# shield_scaffold.net
KiCad netlist of a schematic drawn in EAGLE
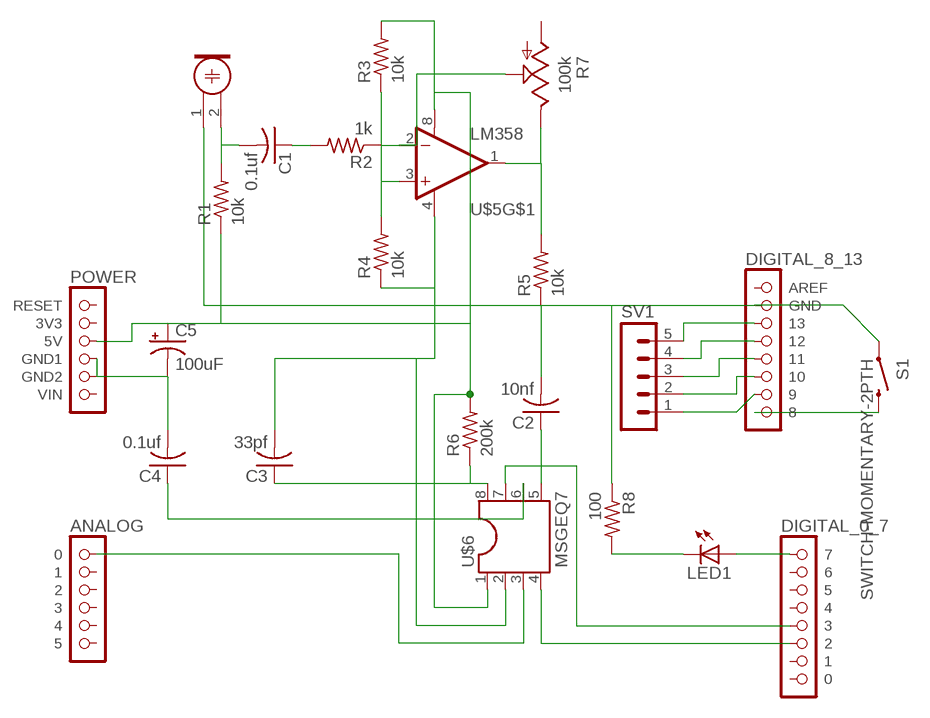
[diagram p0: schematic, sheet 1]

(export (version "E")
  (design (tool "Eeschema 10.0.6"))
  (components
    (comp (ref "C1")
      (value "0.1uf")
      (footprint "eagle-import:C050-030X075")
      (libsource (lib "eagle-import") (part "C-US050-030X075"))
    )
    (comp (ref "C2")
      (value "10nf")
      (footprint "eagle-import:C050-030X075")
      (libsource (lib "eagle-import") (part "C-US050-030X075"))
    )
    (comp (ref "C3")
      (value "33pf")
      (footprint "eagle-import:C050-030X075")
      (libsource (lib "eagle-import") (part "C-US050-030X075"))
    )
    (comp (ref "C4")
      (value "0.1uf")
      (footprint "eagle-import:C050-030X075")
      (libsource (lib "eagle-import") (part "C-US050-030X075"))
    )
    (comp (ref "C5")
      (value "100uF")
      (footprint "eagle-import:E3,5-8")
      (libsource (lib "eagle-import") (part "CPOL-USE3.5-8"))
    )
    (comp (ref "LED1")
      (value "LED3MM")
      (footprint "eagle-import:LED3MM")
      (libsource (lib "eagle-import") (part "LED3MM"))
    )
    (comp (ref "M1")
      (value "ELECTRET_MICROPHON-F6050AP")
      (footprint "eagle-import:F6050AP")
      (libsource (lib "eagle-import") (part "ELECTRET_MICROPHON-F6050AP"))
    )
    (comp (ref "R1")
      (value "10k")
      (footprint "eagle-import:0207_10")
      (libsource (lib "eagle-import") (part "R-US_0207/10"))
    )
    (comp (ref "R2")
      (value "1k")
      (footprint "eagle-import:0207_10")
      (libsource (lib "eagle-import") (part "R-US_0207/10"))
    )
    (comp (ref "R3")
      (value "10k")
      (footprint "eagle-import:0207_10")
      (libsource (lib "eagle-import") (part "R-US_0207/10"))
    )
    (comp (ref "R4")
      (value "10k")
      (footprint "eagle-import:0207_10")
      (libsource (lib "eagle-import") (part "R-US_0207/10"))
    )
    (comp (ref "R5")
      (value "10k")
      (footprint "eagle-import:0207_10")
      (libsource (lib "eagle-import") (part "R-US_0207/10"))
    )
    (comp (ref "R6")
      (value "200k")
      (footprint "eagle-import:0207_10")
      (libsource (lib "eagle-import") (part "R-US_0207/10"))
    )
    (comp (ref "R7")
      (value "100k")
      (footprint "eagle-import:PT-10")
      (libsource (lib "eagle-import") (part "TRIM_US-PT-10"))
    )
    (comp (ref "R8")
      (value "100")
      (footprint "eagle-import:0207_10")
      (libsource (lib "eagle-import") (part "R-US_0207/10"))
    )
    (comp (ref "S1")
      (value "SWITCH-MOMENTARY-2PTH")
      (footprint "eagle-import:TACTILE-PTH")
      (libsource (lib "eagle-import") (part "SWITCH-MOMENTARY-2PTH"))
    )
    (comp (ref "SV1")
      (value "MA05-1")
      (footprint "eagle-import:MA05-1")
      (libsource (lib "eagle-import") (part "MA05-1"))
    )
    (comp (ref "U$1")
      (value "POWER")
      (footprint "eagle-import:1X06")
      (libsource (lib "eagle-import") (part "POWER"))
    )
    (comp (ref "U$2")
      (value "ANALOG")
      (footprint "eagle-import:1X06")
      (libsource (lib "eagle-import") (part "ANALOG"))
    )
    (comp (ref "U$3")
      (value "DIGITAL_0_7")
      (footprint "eagle-import:1X08")
      (libsource (lib "eagle-import") (part "DIGITAL_0_7"))
    )
    (comp (ref "U$4")
      (value "DIGITAL_8_13")
      (footprint "eagle-import:1X08")
      (libsource (lib "eagle-import") (part "DIGITAL_8_13"))
    )
    (comp (ref "U$5")
      (value "LM358")
      (footprint "eagle-import:DIP08")
      (libsource (lib "eagle-import") (part "LM358"))
    )
    (comp (ref "U$6")
      (value "MSGEQ7")
      (footprint "eagle-import:SOCKET-08")
      (libsource (lib "eagle-import") (part "MSGEQ7"))
    )
  )
  (nets
    (net (code "1") (name "/GND") (class "Default")
      (node (ref "C3") (pin "2") (pinfunction "2_2") (pintype "passive"))
      (node (ref "M1") (pin "1") (pinfunction "1_1") (pintype "passive"))
      (node (ref "R4") (pin "1") (pinfunction "1_1") (pintype "passive"))
      (node (ref "R8") (pin "1") (pinfunction "1_1") (pintype "passive"))
      (node (ref "S1") (pin "1") (pinfunction "1_1") (pintype "passive"))
      (node (ref "U$4") (pin "2") (pinfunction "GND_2") (pintype "passive"))
      (node (ref "U$5") (pin "4") (pinfunction "V-_4") (pintype "power_in"))
      (node (ref "U$6") (pin "2") (pinfunction "2_2") (pintype "passive"))
    )
    (net (code "2") (name "Net-(C1-Pad1)") (class "Default")
      (node (ref "C1") (pin "1") (pinfunction "1_1") (pintype "passive"))
      (node (ref "R2") (pin "2") (pinfunction "2_2") (pintype "passive"))
    )
    (net (code "3") (name "Net-(C1-Pad2)") (class "Default")
      (node (ref "C1") (pin "2") (pinfunction "2_2") (pintype "passive"))
      (node (ref "M1") (pin "2") (pinfunction "2_2") (pintype "passive"))
      (node (ref "R1") (pin "2") (pinfunction "2_2") (pintype "passive"))
    )
    (net (code "4") (name "Net-(C2-Pad1)") (class "Default")
      (node (ref "C2") (pin "1") (pinfunction "1_1") (pintype "passive"))
      (node (ref "U$6") (pin "5") (pinfunction "5_5") (pintype "passive"))
    )
    (net (code "5") (name "Net-(C2-Pad2)") (class "Default")
      (node (ref "C2") (pin "2") (pinfunction "2_2") (pintype "passive"))
      (node (ref "R5") (pin "1") (pinfunction "1_1") (pintype "passive"))
    )
    (net (code "6") (name "Net-(C3-Pad1)") (class "Default")
      (node (ref "C3") (pin "1") (pinfunction "1_1") (pintype "passive"))
      (node (ref "R6") (pin "1") (pinfunction "1_1") (pintype "passive"))
      (node (ref "U$6") (pin "8") (pinfunction "8_8") (pintype "passive"))
    )
    (net (code "7") (name "Net-(C4-Pad1)") (class "Default")
      (node (ref "C4") (pin "1") (pinfunction "1_1") (pintype "passive"))
      (node (ref "U$6") (pin "6") (pinfunction "6_6") (pintype "passive"))
    )
    (net (code "8") (name "Net-(LED1-C)") (class "Default")
      (node (ref "LED1") (pin "K") (pinfunction "C_K") (pintype "passive"))
      (node (ref "R8") (pin "2") (pinfunction "2_2") (pintype "passive"))
    )
    (net (code "9") (name "Net-(S1-2)") (class "Default")
      (node (ref "S1") (pin "3") (pinfunction "2_3") (pintype "passive"))
      (node (ref "U$4") (pin "8") (pinfunction "8_8") (pintype "passive"))
    )
    (net (code "10") (name "Net-(U$1-5V)") (class "Default")
      (node (ref "C5") (pin "+") (pinfunction "+_+") (pintype "passive"))
      (node (ref "R1") (pin "1") (pinfunction "1_1") (pintype "passive"))
      (node (ref "R3") (pin "2") (pinfunction "2_2") (pintype "passive"))
      (node (ref "R6") (pin "2") (pinfunction "2_2") (pintype "passive"))
      (node (ref "U$1") (pin "3") (pinfunction "5V_3") (pintype "passive"))
      (node (ref "U$5") (pin "8") (pinfunction "V+_8") (pintype "power_in"))
      (node (ref "U$6") (pin "1") (pinfunction "1_1") (pintype "passive"))
    )
    (net (code "11") (name "Net-(U$1-GND1)") (class "Default")
      (node (ref "C4") (pin "2") (pinfunction "2_2") (pintype "passive"))
      (node (ref "C5") (pin "-") (pinfunction "-_-") (pintype "passive"))
      (node (ref "U$1") (pin "4") (pinfunction "GND1_4") (pintype "passive"))
      (node (ref "U$1") (pin "5") (pinfunction "GND2_5") (pintype "passive"))
    )
    (net (code "12") (name "Net-(U$2-0)") (class "Default")
      (node (ref "U$2") (pin "1") (pinfunction "0_1") (pintype "passive"))
      (node (ref "U$6") (pin "3") (pinfunction "3_3") (pintype "passive"))
    )
    (net (code "13") (name "Net-(U$3-2)") (class "Default")
      (node (ref "U$3") (pin "6") (pinfunction "2_6") (pintype "passive"))
      (node (ref "U$6") (pin "4") (pinfunction "4_4") (pintype "passive"))
    )
    (net (code "14") (name "Net-(U$3-3)") (class "Default")
      (node (ref "U$3") (pin "5") (pinfunction "3_5") (pintype "passive"))
      (node (ref "U$6") (pin "7") (pinfunction "7_7") (pintype "passive"))
    )
    (net (code "15") (name "Net-(U$3-7)") (class "Default")
      (node (ref "LED1") (pin "A") (pinfunction "A_A") (pintype "passive"))
      (node (ref "U$3") (pin "1") (pinfunction "7_1") (pintype "passive"))
    )
    (net (code "16") (name "Net-(U$4-9)") (class "Default")
      (node (ref "SV1") (pin "1") (pinfunction "1_1") (pintype "passive"))
      (node (ref "U$4") (pin "7") (pinfunction "9_7") (pintype "passive"))
    )
    (net (code "17") (name "Net-(U$4-10)") (class "Default")
      (node (ref "SV1") (pin "2") (pinfunction "2_2") (pintype "passive"))
      (node (ref "U$4") (pin "6") (pinfunction "10_6") (pintype "passive"))
    )
    (net (code "18") (name "Net-(U$4-11)") (class "Default")
      (node (ref "SV1") (pin "3") (pinfunction "3_3") (pintype "passive"))
      (node (ref "U$4") (pin "5") (pinfunction "11_5") (pintype "passive"))
    )
    (net (code "19") (name "Net-(U$4-12)") (class "Default")
      (node (ref "SV1") (pin "4") (pinfunction "4_4") (pintype "passive"))
      (node (ref "U$4") (pin "4") (pinfunction "12_4") (pintype "passive"))
    )
    (net (code "20") (name "Net-(U$4-13)") (class "Default")
      (node (ref "SV1") (pin "5") (pinfunction "5_5") (pintype "passive"))
      (node (ref "U$4") (pin "3") (pinfunction "13_3") (pintype "passive"))
    )
    (net (code "21") (name "Net-(U$5A-+IN)") (class "Default")
      (node (ref "R3") (pin "1") (pinfunction "1_1") (pintype "passive"))
      (node (ref "R4") (pin "2") (pinfunction "2_2") (pintype "passive"))
      (node (ref "U$5") (pin "3") (pinfunction "+IN_3") (pintype "input"))
    )
    (net (code "22") (name "Net-(U$5A--IN)") (class "Default")
      (node (ref "R2") (pin "1") (pinfunction "1_1") (pintype "passive"))
      (node (ref "R7") (pin "S") (pinfunction "S_S") (pintype "passive"))
      (node (ref "U$5") (pin "2") (pinfunction "-IN_2") (pintype "input"))
    )
    (net (code "23") (name "Net-(U$5A-OUT)") (class "Default")
      (node (ref "R5") (pin "2") (pinfunction "2_2") (pintype "passive"))
      (node (ref "R7") (pin "E") (pinfunction "E_E") (pintype "passive"))
      (node (ref "U$5") (pin "1") (pinfunction "OUT_1") (pintype "output"))
    )
    (net (code "24") (name "unconnected-(R7-PadA)") (class "Default")
      (node (ref "R7") (pin "A") (pinfunction "A_A") (pintype "passive"))
    )
    (net (code "25") (name "unconnected-(U$1-3V3-Pad2)") (class "Default")
      (node (ref "U$1") (pin "2") (pinfunction "3V3_2") (pintype "passive"))
    )
    (net (code "26") (name "unconnected-(U$1-RESET-Pad1)") (class "Default")
      (node (ref "U$1") (pin "1") (pinfunction "RESET_1") (pintype "passive"))
    )
    (net (code "27") (name "unconnected-(U$1-VIN-Pad6)") (class "Default")
      (node (ref "U$1") (pin "6") (pinfunction "VIN_6") (pintype "passive"))
    )
    (net (code "28") (name "unconnected-(U$2-1-Pad2)") (class "Default")
      (node (ref "U$2") (pin "2") (pinfunction "1_2") (pintype "passive"))
    )
    (net (code "29") (name "unconnected-(U$2-2-Pad3)") (class "Default")
      (node (ref "U$2") (pin "3") (pinfunction "2_3") (pintype "passive"))
    )
    (net (code "30") (name "unconnected-(U$2-3-Pad4)") (class "Default")
      (node (ref "U$2") (pin "4") (pinfunction "3_4") (pintype "passive"))
    )
    (net (code "31") (name "unconnected-(U$2-4-Pad5)") (class "Default")
      (node (ref "U$2") (pin "5") (pinfunction "4_5") (pintype "passive"))
    )
    (net (code "32") (name "unconnected-(U$2-5-Pad6)") (class "Default")
      (node (ref "U$2") (pin "6") (pinfunction "5_6") (pintype "passive"))
    )
    (net (code "33") (name "unconnected-(U$3-0-Pad8)") (class "Default")
      (node (ref "U$3") (pin "8") (pinfunction "0_8") (pintype "passive"))
    )
    (net (code "34") (name "unconnected-(U$3-1-Pad7)") (class "Default")
      (node (ref "U$3") (pin "7") (pinfunction "1_7") (pintype "passive"))
    )
    (net (code "35") (name "unconnected-(U$3-5-Pad3)") (class "Default")
      (node (ref "U$3") (pin "3") (pinfunction "5_3") (pintype "passive"))
    )
    (net (code "36") (name "unconnected-(U$3-6-Pad2)") (class "Default")
      (node (ref "U$3") (pin "2") (pinfunction "6_2") (pintype "passive"))
    )
    (net (code "37") (name "unconnected-(U$3-Pad4)") (class "Default")
      (node (ref "U$3") (pin "4") (pinfunction "4_4") (pintype "passive"))
    )
    (net (code "38") (name "unconnected-(U$4-AREF-Pad1)") (class "Default")
      (node (ref "U$4") (pin "1") (pinfunction "AREF_1") (pintype "passive"))
    )
  )
)
